# SWARMESH.net
KiCad netlist of a schematic drawn in EAGLE
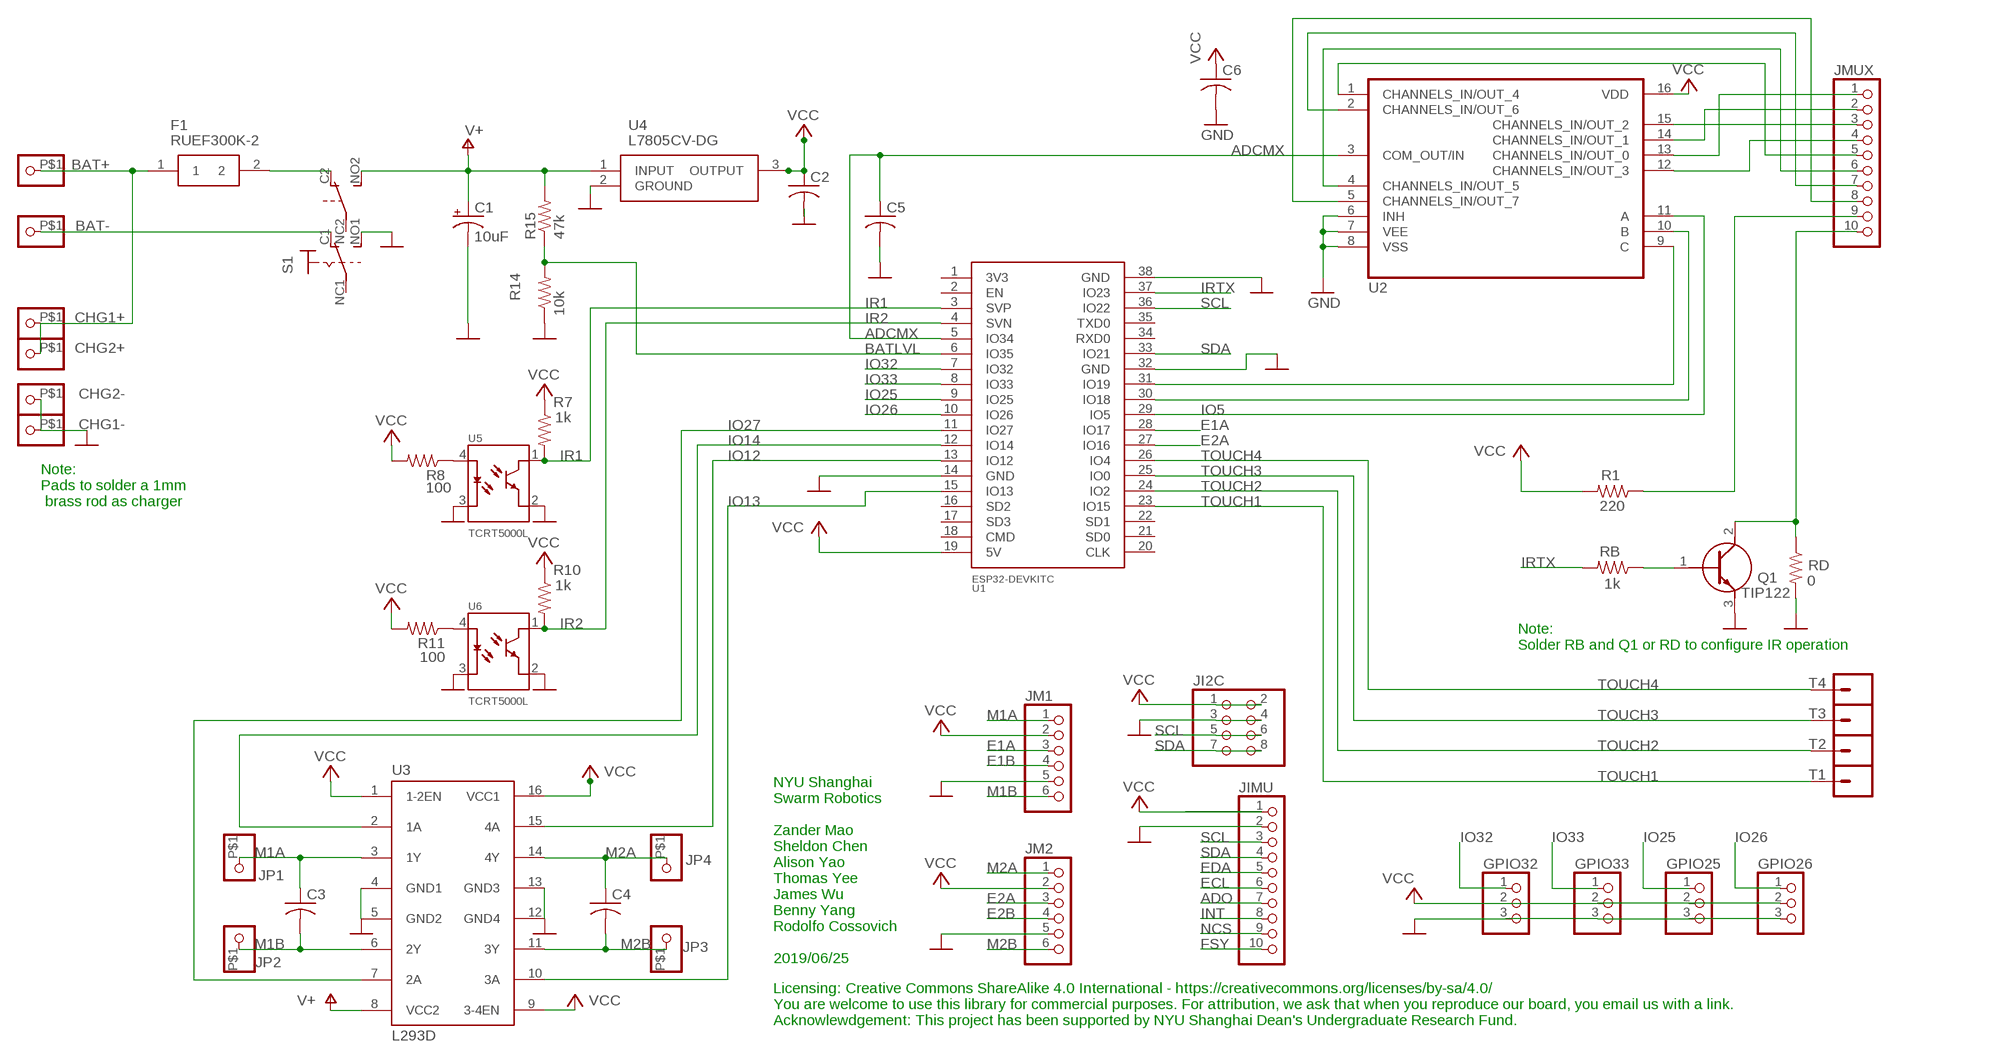
[diagram p0: schematic, sheet 1]

(export (version "E")
  (design (tool "Eeschema 10.0.6"))
  (components
    (comp (ref "BAT+")
      (value "PINHD-1X1-BIGPOGO")
      (footprint "eagle-import:1X1-BIGPOGO")
      (libsource (lib "eagle-import") (part "PINHD-1X1-BIGPOGO"))
    )
    (comp (ref "BAT-")
      (value "PINHD-1X1-BIGPOGO")
      (footprint "eagle-import:1X1-BIGPOGO")
      (libsource (lib "eagle-import") (part "PINHD-1X1-BIGPOGO"))
    )
    (comp (ref "C1")
      (value "10uF")
      (footprint "eagle-import:E2-5")
      (libsource (lib "eagle-import") (part "CPOL-USE2-5"))
    )
    (comp (ref "C2")
      (value "C-US025-030X050")
      (footprint "eagle-import:C025-030X050")
      (libsource (lib "eagle-import") (part "C-US025-030X050"))
    )
    (comp (ref "C3")
      (value "C-US025-025X050")
      (footprint "eagle-import:C025-025X050")
      (libsource (lib "eagle-import") (part "C-US025-025X050"))
    )
    (comp (ref "C4")
      (value "C-US025-025X050")
      (footprint "eagle-import:C025-025X050")
      (libsource (lib "eagle-import") (part "C-US025-025X050"))
    )
    (comp (ref "C5")
      (value "C-US025-030X050")
      (footprint "eagle-import:C025-030X050")
      (libsource (lib "eagle-import") (part "C-US025-030X050"))
    )
    (comp (ref "C6")
      (value "C-US025-025X050")
      (footprint "eagle-import:C025-025X050")
      (libsource (lib "eagle-import") (part "C-US025-025X050"))
    )
    (comp (ref "CHG1+")
      (value "PINHD-1X1-BIGPOGO")
      (footprint "eagle-import:1X1-BIGPOGO")
      (libsource (lib "eagle-import") (part "PINHD-1X1-BIGPOGO"))
    )
    (comp (ref "CHG1-")
      (value "PINHD-1X1-BIGPOGO")
      (footprint "eagle-import:1X1-BIGPOGO")
      (libsource (lib "eagle-import") (part "PINHD-1X1-BIGPOGO"))
    )
    (comp (ref "CHG2+")
      (value "PINHD-1X1-BIGPOGO")
      (footprint "eagle-import:1X1-BIGPOGO")
      (libsource (lib "eagle-import") (part "PINHD-1X1-BIGPOGO"))
    )
    (comp (ref "CHG2-")
      (value "PINHD-1X1-BIGPOGO")
      (footprint "eagle-import:1X1-BIGPOGO")
      (libsource (lib "eagle-import") (part "PINHD-1X1-BIGPOGO"))
    )
    (comp (ref "F1")
      (value "RUEF300K-2")
      (footprint "eagle-import:RUEF300K2")
      (libsource (lib "eagle-import") (part "RUEF300K-2"))
    )
    (comp (ref "GPIO25")
      (value "PINHD-1X3")
      (footprint "eagle-import:1X03")
      (libsource (lib "eagle-import") (part "PINHD-1X3"))
    )
    (comp (ref "GPIO26")
      (value "PINHD-1X3")
      (footprint "eagle-import:1X03")
      (libsource (lib "eagle-import") (part "PINHD-1X3"))
    )
    (comp (ref "GPIO32")
      (value "PINHD-1X3")
      (footprint "eagle-import:1X03")
      (libsource (lib "eagle-import") (part "PINHD-1X3"))
    )
    (comp (ref "GPIO33")
      (value "PINHD-1X3")
      (footprint "eagle-import:1X03")
      (libsource (lib "eagle-import") (part "PINHD-1X3"))
    )
    (comp (ref "JI2C")
      (value "PINHD-2X4")
      (footprint "eagle-import:2X04")
      (libsource (lib "eagle-import") (part "PINHD-2X4"))
    )
    (comp (ref "JIMU")
      (value "PINHD-1X10")
      (footprint "eagle-import:1X10-BIG")
      (libsource (lib "eagle-import") (part "PINHD-1X10"))
    )
    (comp (ref "JM1")
      (value "PINHD-1X6")
      (footprint "eagle-import:1X06")
      (libsource (lib "eagle-import") (part "PINHD-1X6"))
    )
    (comp (ref "JM2")
      (value "PINHD-1X6")
      (footprint "eagle-import:1X06")
      (libsource (lib "eagle-import") (part "PINHD-1X6"))
    )
    (comp (ref "JMUX")
      (value "PINHD-1X10")
      (footprint "eagle-import:1X10-BIG")
      (libsource (lib "eagle-import") (part "PINHD-1X10"))
    )
    (comp (ref "JP1")
      (value "PINHD-1X1-BIGPOGO")
      (footprint "eagle-import:1X1-BIGPOGO")
      (libsource (lib "eagle-import") (part "adafruit_420_PINHD-1X1-BIGPOGO"))
    )
    (comp (ref "JP2")
      (value "PINHD-1X1-BIGPOGO")
      (footprint "eagle-import:1X1-BIGPOGO")
      (libsource (lib "eagle-import") (part "adafruit_420_PINHD-1X1-BIGPOGO"))
    )
    (comp (ref "JP3")
      (value "PINHD-1X1-BIGPOGO")
      (footprint "eagle-import:1X1-BIGPOGO")
      (libsource (lib "eagle-import") (part "adafruit_420_PINHD-1X1-BIGPOGO"))
    )
    (comp (ref "JP4")
      (value "PINHD-1X1-BIGPOGO")
      (footprint "eagle-import:1X1-BIGPOGO")
      (libsource (lib "eagle-import") (part "adafruit_420_PINHD-1X1-BIGPOGO"))
    )
    (comp (ref "Q1")
      (value "TIP122")
      (footprint "eagle-import:TO270P460X1020X2008-3P")
      (fields (field (name "MOUSER_PART_NUMBER") "511-TIP122"))
      (libsource (lib "eagle-import") (part "TIP122"))
    )
    (comp (ref "R1")
      (value "220")
      (footprint "eagle-import:0207_9")
      (libsource (lib "eagle-import") (part "R-US_0207/9"))
    )
    (comp (ref "R7")
      (value "1k")
      (footprint "eagle-import:0207_9")
      (libsource (lib "eagle-import") (part "R-US_0207/9"))
    )
    (comp (ref "R8")
      (value "100")
      (footprint "eagle-import:0207_9")
      (libsource (lib "eagle-import") (part "R-US_0207/9"))
    )
    (comp (ref "R10")
      (value "1k")
      (footprint "eagle-import:0207_9")
      (libsource (lib "eagle-import") (part "R-US_0207/9"))
    )
    (comp (ref "R11")
      (value "100")
      (footprint "eagle-import:0207_9")
      (libsource (lib "eagle-import") (part "R-US_0207/9"))
    )
    (comp (ref "R14")
      (value "10k")
      (footprint "eagle-import:0207_9")
      (libsource (lib "eagle-import") (part "R-US_0207/9"))
    )
    (comp (ref "R15")
      (value "47k")
      (footprint "eagle-import:0207_9")
      (libsource (lib "eagle-import") (part "R-US_0207/9"))
    )
    (comp (ref "RB")
      (value "1k")
      (footprint "eagle-import:0207_9")
      (libsource (lib "eagle-import") (part "R-US_0207/9"))
    )
    (comp (ref "RD")
      (value "0")
      (footprint "eagle-import:0207_9")
      (libsource (lib "eagle-import") (part "R-US_0207/9"))
    )
    (comp (ref "S1")
      (value "SWITCH_320-938")
      (footprint "eagle-import:PS22F03")
      (libsource (lib "eagle-import") (part "SWITCH_320-938"))
    )
    (comp (ref "T1")
      (value "CONN_01SPRING-CONN")
      (footprint "eagle-import:SPRING-CONNECTOR")
      (libsource (lib "eagle-import") (part "CONN_01SPRING-CONN"))
    )
    (comp (ref "T2")
      (value "CONN_01SPRING-CONN")
      (footprint "eagle-import:SPRING-CONNECTOR")
      (libsource (lib "eagle-import") (part "CONN_01SPRING-CONN"))
    )
    (comp (ref "T3")
      (value "CONN_01SPRING-CONN")
      (footprint "eagle-import:SPRING-CONNECTOR")
      (libsource (lib "eagle-import") (part "CONN_01SPRING-CONN"))
    )
    (comp (ref "T4")
      (value "CONN_01SPRING-CONN")
      (footprint "eagle-import:SPRING-CONNECTOR")
      (libsource (lib "eagle-import") (part "CONN_01SPRING-CONN"))
    )
    (comp (ref "U1")
      (value "ESP32DEVKITC")
      (footprint "eagle-import:ESP32-DEVKITC")
      (libsource (lib "eagle-import") (part "ESP32DEVKITC"))
    )
    (comp (ref "U2")
      (value "CD4051BEE4")
      (footprint "eagle-import:CD4051BEE4DIP")
      (libsource (lib "eagle-import") (part "CD4051BEE4"))
    )
    (comp (ref "U3")
      (value "L293D")
      (footprint "eagle-import:DIL16")
      (libsource (lib "eagle-import") (part "L293D"))
    )
    (comp (ref "U4")
      (value "L7805CV-DG")
      (footprint "eagle-import:TO270P460X1020X2008-3P")
      (fields (field (name "MOUSER_PART_NUMBER") "511-L7805CV-DG") (field (name "RS_PART_NUMBER") "7931346P"))
      (libsource (lib "eagle-import") (part "L7805CV-DG"))
    )
    (comp (ref "U5")
      (value "TCRT5000L")
      (footprint "eagle-import:XDCR_TCRT5000L")
      (fields (field (name "MF") "Vishay Semiconductor"))
      (libsource (lib "eagle-import") (part "TCRT5000L"))
    )
    (comp (ref "U6")
      (value "TCRT5000L")
      (footprint "eagle-import:XDCR_TCRT5000L")
      (fields (field (name "MF") "Vishay Semiconductor"))
      (libsource (lib "eagle-import") (part "TCRT5000L"))
    )
  )
  (nets
    (net (code "1") (name "/ADCMX") (class "Default")
      (node (ref "C5") (pin "1") (pinfunction "1_1") (pintype "passive"))
      (node (ref "U1") (pin "5") (pinfunction "IO34_5") (pintype "bidirectional"))
      (node (ref "U2") (pin "3") (pinfunction "COM_OUT/IN_3") (pintype "bidirectional"))
    )
    (net (code "2") (name "/ADO") (class "Default")
      (node (ref "JIMU") (pin "7") (pinfunction "7_7") (pintype "passive"))
    )
    (net (code "3") (name "/BATLVL") (class "Default")
      (node (ref "R14") (pin "2") (pinfunction "2_2") (pintype "passive"))
      (node (ref "R15") (pin "1") (pinfunction "1_1") (pintype "passive"))
      (node (ref "U1") (pin "6") (pinfunction "IO35_6") (pintype "bidirectional"))
    )
    (net (code "4") (name "/E1A") (class "Default")
      (node (ref "JM1") (pin "3") (pinfunction "3_3") (pintype "passive"))
      (node (ref "U1") (pin "28") (pinfunction "IO17_28") (pintype "bidirectional"))
    )
    (net (code "5") (name "/E1B") (class "Default")
      (node (ref "JM1") (pin "4") (pinfunction "4_4") (pintype "passive"))
    )
    (net (code "6") (name "/E2A") (class "Default")
      (node (ref "JM2") (pin "3") (pinfunction "3_3") (pintype "passive"))
      (node (ref "U1") (pin "27") (pinfunction "IO16_27") (pintype "bidirectional"))
    )
    (net (code "7") (name "/E2B") (class "Default")
      (node (ref "JM2") (pin "4") (pinfunction "4_4") (pintype "passive"))
    )
    (net (code "8") (name "/ECL") (class "Default")
      (node (ref "JIMU") (pin "6") (pinfunction "6_6") (pintype "passive"))
    )
    (net (code "9") (name "/EDA") (class "Default")
      (node (ref "JIMU") (pin "5") (pinfunction "5_5") (pintype "passive"))
    )
    (net (code "10") (name "/FSY") (class "Default")
      (node (ref "JIMU") (pin "10") (pinfunction "10_10") (pintype "passive"))
    )
    (net (code "11") (name "/INT") (class "Default")
      (node (ref "JIMU") (pin "8") (pinfunction "8_8") (pintype "passive"))
    )
    (net (code "12") (name "/IO5") (class "Default")
      (node (ref "U1") (pin "29") (pinfunction "IO5_29") (pintype "bidirectional"))
      (node (ref "U2") (pin "11") (pinfunction "A_11") (pintype "input"))
    )
    (net (code "13") (name "/IO12") (class "Default")
      (node (ref "U1") (pin "13") (pinfunction "IO12_13") (pintype "bidirectional"))
      (node (ref "U3") (pin "15") (pinfunction "4A_15") (pintype "input"))
    )
    (net (code "14") (name "/IO13") (class "Default")
      (node (ref "U1") (pin "15") (pinfunction "IO13_15") (pintype "bidirectional"))
      (node (ref "U3") (pin "10") (pinfunction "3A_10") (pintype "input"))
    )
    (net (code "15") (name "/IO14") (class "Default")
      (node (ref "U1") (pin "12") (pinfunction "IO14_12") (pintype "bidirectional"))
      (node (ref "U3") (pin "2") (pinfunction "1A_2") (pintype "input"))
    )
    (net (code "16") (name "/IO25") (class "Default")
      (node (ref "GPIO25") (pin "1") (pinfunction "1_1") (pintype "passive"))
      (node (ref "U1") (pin "9") (pinfunction "IO25_9") (pintype "bidirectional"))
    )
    (net (code "17") (name "/IO26") (class "Default")
      (node (ref "GPIO26") (pin "1") (pinfunction "1_1") (pintype "passive"))
      (node (ref "U1") (pin "10") (pinfunction "IO26_10") (pintype "bidirectional"))
    )
    (net (code "18") (name "/IO27") (class "Default")
      (node (ref "U1") (pin "11") (pinfunction "IO27_11") (pintype "bidirectional"))
      (node (ref "U3") (pin "7") (pinfunction "2A_7") (pintype "input"))
    )
    (net (code "19") (name "/IO32") (class "Default")
      (node (ref "GPIO32") (pin "1") (pinfunction "1_1") (pintype "passive"))
      (node (ref "U1") (pin "7") (pinfunction "IO32_7") (pintype "bidirectional"))
    )
    (net (code "20") (name "/IO33") (class "Default")
      (node (ref "GPIO33") (pin "1") (pinfunction "1_1") (pintype "passive"))
      (node (ref "U1") (pin "8") (pinfunction "IO33_8") (pintype "bidirectional"))
    )
    (net (code "21") (name "/IR1") (class "Default")
      (node (ref "R7") (pin "2") (pinfunction "2_2") (pintype "passive"))
      (node (ref "U1") (pin "3") (pinfunction "SVP_3") (pintype "bidirectional"))
      (node (ref "U5") (pin "1") (pinfunction "CO_1") (pintype "passive"))
    )
    (net (code "22") (name "/IR2") (class "Default")
      (node (ref "R10") (pin "2") (pinfunction "2_2") (pintype "passive"))
      (node (ref "U1") (pin "4") (pinfunction "SVN_4") (pintype "bidirectional"))
      (node (ref "U6") (pin "1") (pinfunction "CO_1") (pintype "passive"))
    )
    (net (code "23") (name "/IRTX") (class "Default")
      (node (ref "RB") (pin "2") (pinfunction "2_2") (pintype "passive"))
      (node (ref "U1") (pin "37") (pinfunction "IO23_37") (pintype "bidirectional"))
    )
    (net (code "24") (name "/M1A") (class "Default")
      (node (ref "C3") (pin "1") (pinfunction "1_1") (pintype "passive"))
      (node (ref "JM1") (pin "1") (pinfunction "1_1") (pintype "passive"))
      (node (ref "JP1") (pin "P$1") (pinfunction "1_P$1") (pintype "passive"))
      (node (ref "U3") (pin "3") (pinfunction "1Y_3") (pintype "output"))
    )
    (net (code "25") (name "/M1B") (class "Default")
      (node (ref "C3") (pin "2") (pinfunction "2_2") (pintype "passive"))
      (node (ref "JM1") (pin "6") (pinfunction "6_6") (pintype "passive"))
      (node (ref "JP2") (pin "P$1") (pinfunction "1_P$1") (pintype "passive"))
      (node (ref "U3") (pin "6") (pinfunction "2Y_6") (pintype "output"))
    )
    (net (code "26") (name "/M2A") (class "Default")
      (node (ref "C4") (pin "1") (pinfunction "1_1") (pintype "passive"))
      (node (ref "JM2") (pin "1") (pinfunction "1_1") (pintype "passive"))
      (node (ref "JP4") (pin "P$1") (pinfunction "1_P$1") (pintype "passive"))
      (node (ref "U3") (pin "14") (pinfunction "4Y_14") (pintype "output"))
    )
    (net (code "27") (name "/M2B") (class "Default")
      (node (ref "C4") (pin "2") (pinfunction "2_2") (pintype "passive"))
      (node (ref "JM2") (pin "6") (pinfunction "6_6") (pintype "passive"))
      (node (ref "JP3") (pin "P$1") (pinfunction "1_P$1") (pintype "passive"))
      (node (ref "U3") (pin "11") (pinfunction "3Y_11") (pintype "output"))
    )
    (net (code "28") (name "/NCS") (class "Default")
      (node (ref "JIMU") (pin "9") (pinfunction "9_9") (pintype "passive"))
    )
    (net (code "29") (name "/SCL") (class "Default")
      (node (ref "JI2C") (pin "5") (pinfunction "5_5") (pintype "passive"))
      (node (ref "JI2C") (pin "6") (pinfunction "6_6") (pintype "passive"))
      (node (ref "JIMU") (pin "3") (pinfunction "3_3") (pintype "passive"))
      (node (ref "U1") (pin "36") (pinfunction "IO22_36") (pintype "bidirectional"))
    )
    (net (code "30") (name "/SDA") (class "Default")
      (node (ref "JI2C") (pin "7") (pinfunction "7_7") (pintype "passive"))
      (node (ref "JI2C") (pin "8") (pinfunction "8_8") (pintype "passive"))
      (node (ref "JIMU") (pin "4") (pinfunction "4_4") (pintype "passive"))
      (node (ref "U1") (pin "33") (pinfunction "IO21_33") (pintype "bidirectional"))
    )
    (net (code "31") (name "/TOUCH1") (class "Default")
      (node (ref "T1") (pin "P$2") (pinfunction "1_P$2") (pintype "passive"))
      (node (ref "U1") (pin "23") (pinfunction "IO15_23") (pintype "bidirectional"))
    )
    (net (code "32") (name "/TOUCH2") (class "Default")
      (node (ref "T2") (pin "P$2") (pinfunction "1_P$2") (pintype "passive"))
      (node (ref "U1") (pin "24") (pinfunction "IO2_24") (pintype "bidirectional"))
    )
    (net (code "33") (name "/TOUCH3") (class "Default")
      (node (ref "T3") (pin "P$2") (pinfunction "1_P$2") (pintype "passive"))
      (node (ref "U1") (pin "25") (pinfunction "IO0_25") (pintype "bidirectional"))
    )
    (net (code "34") (name "/TOUCH4") (class "Default")
      (node (ref "T4") (pin "P$2") (pinfunction "1_P$2") (pintype "passive"))
      (node (ref "U1") (pin "26") (pinfunction "IO4_26") (pintype "bidirectional"))
    )
    (net (code "35") (name "GND") (class "Default")
      (node (ref "C1") (pin "-") (pinfunction "-_-") (pintype "passive"))
      (node (ref "C2") (pin "2") (pinfunction "2_2") (pintype "passive"))
      (node (ref "C5") (pin "2") (pinfunction "2_2") (pintype "passive"))
      (node (ref "C6") (pin "2") (pinfunction "2_2") (pintype "passive"))
      (node (ref "CHG1-") (pin "P$1") (pinfunction "1_P$1") (pintype "passive"))
      (node (ref "CHG2-") (pin "P$1") (pinfunction "1_P$1") (pintype "passive"))
      (node (ref "GPIO25") (pin "3") (pinfunction "3_3") (pintype "passive"))
      (node (ref "GPIO26") (pin "3") (pinfunction "3_3") (pintype "passive"))
      (node (ref "GPIO32") (pin "3") (pinfunction "3_3") (pintype "passive"))
      (node (ref "GPIO33") (pin "3") (pinfunction "3_3") (pintype "passive"))
      (node (ref "JI2C") (pin "3") (pinfunction "3_3") (pintype "passive"))
      (node (ref "JI2C") (pin "4") (pinfunction "4_4") (pintype "passive"))
      (node (ref "JIMU") (pin "2") (pinfunction "2_2") (pintype "passive"))
      (node (ref "JM1") (pin "5") (pinfunction "5_5") (pintype "passive"))
      (node (ref "JM2") (pin "5") (pinfunction "5_5") (pintype "passive"))
      (node (ref "Q1") (pin "3") (pinfunction "E_3") (pintype "bidirectional"))
      (node (ref "R14") (pin "1") (pinfunction "1_1") (pintype "passive"))
      (node (ref "RD") (pin "2") (pinfunction "2_2") (pintype "passive"))
      (node (ref "S1") (pin "NO1") (pinfunction "S_NO1") (pintype "passive"))
      (node (ref "U1") (pin "14") (pinfunction "GND_14") (pintype "bidirectional"))
      (node (ref "U1") (pin "32") (pinfunction "GND_32") (pintype "bidirectional"))
      (node (ref "U1") (pin "38") (pinfunction "GND_38") (pintype "bidirectional"))
      (node (ref "U2") (pin "6") (pinfunction "INH_6") (pintype "input"))
      (node (ref "U2") (pin "7") (pinfunction "VEE_7") (pintype "power_in"))
      (node (ref "U2") (pin "8") (pinfunction "VSS_8") (pintype "power_in"))
      (node (ref "U3") (pin "12") (pinfunction "GND4_12") (pintype "power_in"))
      (node (ref "U3") (pin "13") (pinfunction "GND3_13") (pintype "power_in"))
      (node (ref "U3") (pin "4") (pinfunction "GND1_4") (pintype "power_in"))
      (node (ref "U3") (pin "5") (pinfunction "GND2_5") (pintype "power_in"))
      (node (ref "U4") (pin "2") (pinfunction "GROUND_2") (pintype "bidirectional"))
      (node (ref "U5") (pin "2") (pinfunction "E_2") (pintype "passive"))
      (node (ref "U5") (pin "3") (pinfunction "C_3") (pintype "passive"))
      (node (ref "U6") (pin "2") (pinfunction "E_2") (pintype "passive"))
      (node (ref "U6") (pin "3") (pinfunction "C_3") (pintype "passive"))
    )
    (net (code "36") (name "Net-(BAT+-1)") (class "Default")
      (node (ref "BAT+") (pin "P$1") (pinfunction "1_P$1") (pintype "passive"))
      (node (ref "CHG1+") (pin "P$1") (pinfunction "1_P$1") (pintype "passive"))
      (node (ref "CHG2+") (pin "P$1") (pinfunction "1_P$1") (pintype "passive"))
      (node (ref "F1") (pin "1") (pinfunction "1_1") (pintype "bidirectional"))
    )
    (net (code "37") (name "Net-(BAT--1)") (class "Default")
      (node (ref "BAT-") (pin "P$1") (pinfunction "1_P$1") (pintype "passive"))
      (node (ref "S1") (pin "C1") (pinfunction "O_C1") (pintype "passive"))
    )
    (net (code "38") (name "Net-(JMUX-Pad9)") (class "Default")
      (node (ref "JMUX") (pin "9") (pinfunction "9_9") (pintype "passive"))
      (node (ref "R1") (pin "1") (pinfunction "1_1") (pintype "passive"))
    )
    (net (code "39") (name "Net-(Q1-B)") (class "Default")
      (node (ref "Q1") (pin "1") (pinfunction "B_1") (pintype "bidirectional"))
      (node (ref "RB") (pin "1") (pinfunction "1_1") (pintype "passive"))
    )
    (net (code "40") (name "Net-(Q1-C)") (class "Default")
      (node (ref "JMUX") (pin "10") (pinfunction "10_10") (pintype "passive"))
      (node (ref "Q1") (pin "2") (pinfunction "C_2") (pintype "bidirectional"))
      (node (ref "RD") (pin "1") (pinfunction "1_1") (pintype "passive"))
    )
    (net (code "41") (name "Net-(S1B-O)") (class "Default")
      (node (ref "F1") (pin "2") (pinfunction "2_2") (pintype "bidirectional"))
      (node (ref "S1") (pin "C2") (pinfunction "O_C2") (pintype "passive"))
    )
    (net (code "42") (name "Net-(U1-IO18)") (class "Default")
      (node (ref "U1") (pin "30") (pinfunction "IO18_30") (pintype "bidirectional"))
      (node (ref "U2") (pin "10") (pinfunction "B_10") (pintype "input"))
    )
    (net (code "43") (name "Net-(U1-IO19)") (class "Default")
      (node (ref "U1") (pin "31") (pinfunction "IO19_31") (pintype "bidirectional"))
      (node (ref "U2") (pin "9") (pinfunction "C_9") (pintype "input"))
    )
    (net (code "44") (name "Net-(U2-CHANNELS_IN{slash}OUT_0)") (class "Default")
      (node (ref "JMUX") (pin "1") (pinfunction "1_1") (pintype "passive"))
      (node (ref "U2") (pin "13") (pinfunction "CHANNELS_IN/OUT_0_13") (pintype "bidirectional"))
    )
    (net (code "45") (name "Net-(U2-CHANNELS_IN{slash}OUT_1)") (class "Default")
      (node (ref "JMUX") (pin "2") (pinfunction "2_2") (pintype "passive"))
      (node (ref "U2") (pin "14") (pinfunction "CHANNELS_IN/OUT_1_14") (pintype "bidirectional"))
    )
    (net (code "46") (name "Net-(U2-CHANNELS_IN{slash}OUT_2)") (class "Default")
      (node (ref "JMUX") (pin "3") (pinfunction "3_3") (pintype "passive"))
      (node (ref "U2") (pin "15") (pinfunction "CHANNELS_IN/OUT_2_15") (pintype "bidirectional"))
    )
    (net (code "47") (name "Net-(U2-CHANNELS_IN{slash}OUT_3)") (class "Default")
      (node (ref "JMUX") (pin "4") (pinfunction "4_4") (pintype "passive"))
      (node (ref "U2") (pin "12") (pinfunction "CHANNELS_IN/OUT_3_12") (pintype "bidirectional"))
    )
    (net (code "48") (name "Net-(U2-CHANNELS_IN{slash}OUT_4)") (class "Default")
      (node (ref "JMUX") (pin "5") (pinfunction "5_5") (pintype "passive"))
      (node (ref "U2") (pin "1") (pinfunction "CHANNELS_IN/OUT_4_1") (pintype "bidirectional"))
    )
    (net (code "49") (name "Net-(U2-CHANNELS_IN{slash}OUT_5)") (class "Default")
      (node (ref "JMUX") (pin "6") (pinfunction "6_6") (pintype "passive"))
      (node (ref "U2") (pin "4") (pinfunction "CHANNELS_IN/OUT_5_4") (pintype "bidirectional"))
    )
    (net (code "50") (name "Net-(U2-CHANNELS_IN{slash}OUT_6)") (class "Default")
      (node (ref "JMUX") (pin "7") (pinfunction "7_7") (pintype "passive"))
      (node (ref "U2") (pin "2") (pinfunction "CHANNELS_IN/OUT_6_2") (pintype "bidirectional"))
    )
    (net (code "51") (name "Net-(U2-CHANNELS_IN{slash}OUT_7)") (class "Default")
      (node (ref "JMUX") (pin "8") (pinfunction "8_8") (pintype "passive"))
      (node (ref "U2") (pin "5") (pinfunction "CHANNELS_IN/OUT_7_5") (pintype "bidirectional"))
    )
    (net (code "52") (name "Net-(U5-A)") (class "Default")
      (node (ref "R8") (pin "1") (pinfunction "1_1") (pintype "passive"))
      (node (ref "U5") (pin "4") (pinfunction "A_4") (pintype "passive"))
    )
    (net (code "53") (name "Net-(U6-A)") (class "Default")
      (node (ref "R11") (pin "1") (pinfunction "1_1") (pintype "passive"))
      (node (ref "U6") (pin "4") (pinfunction "A_4") (pintype "passive"))
    )
    (net (code "54") (name "V+") (class "Default")
      (node (ref "C1") (pin "+") (pinfunction "+_+") (pintype "passive"))
      (node (ref "R15") (pin "2") (pinfunction "2_2") (pintype "passive"))
      (node (ref "S1") (pin "NO2") (pinfunction "S_NO2") (pintype "passive"))
      (node (ref "U3") (pin "8") (pinfunction "VCC2_8") (pintype "power_in"))
      (node (ref "U4") (pin "1") (pinfunction "INPUT_1") (pintype "input"))
    )
    (net (code "55") (name "VCC") (class "Default")
      (node (ref "C2") (pin "1") (pinfunction "1_1") (pintype "passive"))
      (node (ref "C6") (pin "1") (pinfunction "1_1") (pintype "passive"))
      (node (ref "GPIO25") (pin "2") (pinfunction "2_2") (pintype "passive"))
      (node (ref "GPIO26") (pin "2") (pinfunction "2_2") (pintype "passive"))
      (node (ref "GPIO32") (pin "2") (pinfunction "2_2") (pintype "passive"))
      (node (ref "GPIO33") (pin "2") (pinfunction "2_2") (pintype "passive"))
      (node (ref "JI2C") (pin "1") (pinfunction "1_1") (pintype "passive"))
      (node (ref "JI2C") (pin "2") (pinfunction "2_2") (pintype "passive"))
      (node (ref "JIMU") (pin "1") (pinfunction "1_1") (pintype "passive"))
      (node (ref "JM1") (pin "2") (pinfunction "2_2") (pintype "passive"))
      (node (ref "JM2") (pin "2") (pinfunction "2_2") (pintype "passive"))
      (node (ref "R1") (pin "2") (pinfunction "2_2") (pintype "passive"))
      (node (ref "R10") (pin "1") (pinfunction "1_1") (pintype "passive"))
      (node (ref "R11") (pin "2") (pinfunction "2_2") (pintype "passive"))
      (node (ref "R7") (pin "1") (pinfunction "1_1") (pintype "passive"))
      (node (ref "R8") (pin "2") (pinfunction "2_2") (pintype "passive"))
      (node (ref "U1") (pin "19") (pinfunction "5V_19") (pintype "bidirectional"))
      (node (ref "U2") (pin "16") (pinfunction "VDD_16") (pintype "power_in"))
      (node (ref "U3") (pin "1") (pinfunction "1-2EN_1") (pintype "input"))
      (node (ref "U3") (pin "16") (pinfunction "VCC1_16") (pintype "power_in"))
      (node (ref "U3") (pin "9") (pinfunction "3-4EN_9") (pintype "input"))
      (node (ref "U4") (pin "3") (pinfunction "OUTPUT_3") (pintype "output"))
    )
    (net (code "56") (name "unconnected-(S1A-P-PadNC1)") (class "Default")
      (node (ref "S1") (pin "NC1") (pinfunction "P_NC1") (pintype "passive"))
    )
    (net (code "57") (name "unconnected-(S1B-P-PadNC2)") (class "Default")
      (node (ref "S1") (pin "NC2") (pinfunction "P_NC2") (pintype "passive"))
    )
    (net (code "58") (name "unconnected-(U1-3V3-Pad1)") (class "Default")
      (node (ref "U1") (pin "1") (pinfunction "3V3_1") (pintype "bidirectional"))
    )
    (net (code "59") (name "unconnected-(U1-CLK-Pad20)") (class "Default")
      (node (ref "U1") (pin "20") (pinfunction "CLK_20") (pintype "bidirectional"))
    )
    (net (code "60") (name "unconnected-(U1-CMD-Pad18)") (class "Default")
      (node (ref "U1") (pin "18") (pinfunction "CMD_18") (pintype "bidirectional"))
    )
    (net (code "61") (name "unconnected-(U1-EN-Pad2)") (class "Default")
      (node (ref "U1") (pin "2") (pinfunction "EN_2") (pintype "bidirectional"))
    )
    (net (code "62") (name "unconnected-(U1-RXD0-Pad34)") (class "Default")
      (node (ref "U1") (pin "34") (pinfunction "RXD0_34") (pintype "bidirectional"))
    )
    (net (code "63") (name "unconnected-(U1-SD0-Pad21)") (class "Default")
      (node (ref "U1") (pin "21") (pinfunction "SD0_21") (pintype "bidirectional"))
    )
    (net (code "64") (name "unconnected-(U1-SD1-Pad22)") (class "Default")
      (node (ref "U1") (pin "22") (pinfunction "SD1_22") (pintype "bidirectional"))
    )
    (net (code "65") (name "unconnected-(U1-SD2-Pad16)") (class "Default")
      (node (ref "U1") (pin "16") (pinfunction "SD2_16") (pintype "bidirectional"))
    )
    (net (code "66") (name "unconnected-(U1-SD3-Pad17)") (class "Default")
      (node (ref "U1") (pin "17") (pinfunction "SD3_17") (pintype "bidirectional"))
    )
    (net (code "67") (name "unconnected-(U1-TXD0-Pad35)") (class "Default")
      (node (ref "U1") (pin "35") (pinfunction "TXD0_35") (pintype "bidirectional"))
    )
  )
)
